# keycontrol2.net
KiCad netlist of a schematic drawn in Altium Designer
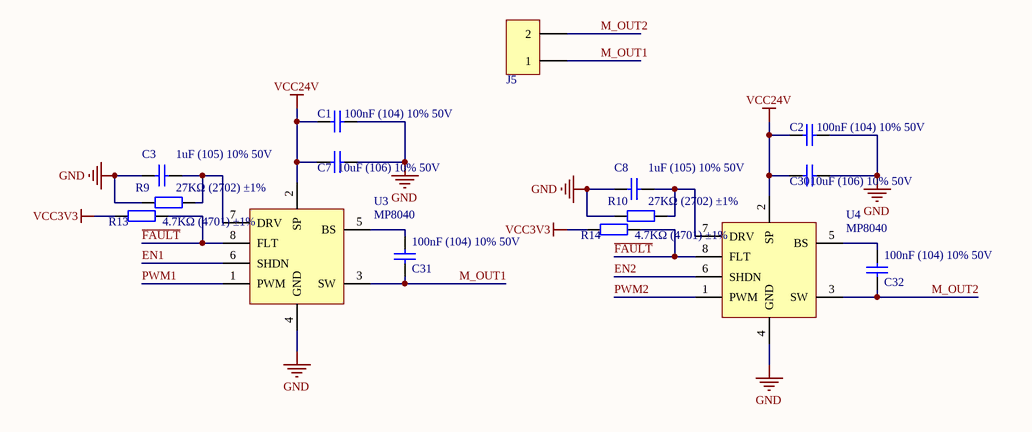
[diagram p0: keycontrol2.SchDoc]

(export (version "E")
  (design (tool "Eeschema 10.0.6"))
  (components
    (comp (ref "C1")
      (value "100nF (104) 10% 50V")
      (footprint "0603_C")
      (description "贴片电容")
      (libsource (lib "AD封装2018.9.19Miscellaneous Devices LC") (part "0603 100nF (104) 10% 50V"))
    )
    (comp (ref "C2")
      (value "100nF (104) 10% 50V")
      (footprint "0603_C")
      (description "贴片电容")
      (libsource (lib "AD封装2018.9.19Miscellaneous Devices LC") (part "0603 100nF (104) 10% 50V"))
    )
    (comp (ref "C3")
      (value "1uF (105) 10% 50V")
      (footprint "0603_C")
      (description "贴片电容")
      (libsource (lib "AD封装2018.9.19Miscellaneous Devices LC") (part "0603 1uF (105) 10% 50V"))
    )
    (comp (ref "C7")
      (value "10uF (106) 10% 50V")
      (footprint "1206_C")
      (description "贴片电容")
      (libsource (lib "AD封装2018.9.19Miscellaneous Devices LC") (part "1206 10uF (106) 10% 50V"))
    )
    (comp (ref "C8")
      (value "1uF (105) 10% 50V")
      (footprint "0603_C")
      (description "贴片电容")
      (libsource (lib "AD封装2018.9.19Miscellaneous Devices LC") (part "0603 1uF (105) 10% 50V"))
    )
    (comp (ref "C30")
      (value "10uF (106) 10% 50V")
      (footprint "1206_C")
      (description "贴片电容")
      (libsource (lib "AD封装2018.9.19Miscellaneous Devices LC") (part "1206 10uF (106) 10% 50V"))
    )
    (comp (ref "C31")
      (value "100nF (104) 10% 50V")
      (footprint "0603_C")
      (description "贴片电容")
      (libsource (lib "AD封装2018.9.19Miscellaneous Devices LC") (part "0603 100nF (104) 10% 50V"))
    )
    (comp (ref "C32")
      (value "100nF (104) 10% 50V")
      (footprint "0603_C")
      (description "贴片电容")
      (libsource (lib "AD封装2018.9.19Miscellaneous Devices LC") (part "0603 100nF (104) 10% 50V"))
    )
    (comp (ref "J5") (value "MOTOR") (footprint "XH-2P") (libsource (lib "我的集成库") (part "header2")))
    (comp (ref "R9")
      (value "27KΩ (2702) ±1%")
      (footprint "0603_R")
      (description "贴片电阻")
      (libsource (lib "AD封装2018.9.19Miscellaneous Devices LC") (part "0603 27KΩ (2702) 1%"))
    )
    (comp (ref "R10")
      (value "27KΩ (2702) ±1%")
      (footprint "0603_R")
      (description "贴片电阻")
      (libsource (lib "AD封装2018.9.19Miscellaneous Devices LC") (part "0603 27KΩ (2702) 1%"))
    )
    (comp (ref "R13")
      (value "4.7KΩ (4701) ±1%")
      (footprint "0603_R")
      (description "贴片电阻")
      (libsource (lib "AD封装2018.9.19Miscellaneous Devices LC") (part "0603 4.7KΩ (4701) 1%"))
    )
    (comp (ref "R14")
      (value "4.7KΩ (4701) ±1%")
      (footprint "0603_R")
      (description "贴片电阻")
      (libsource (lib "AD封装2018.9.19Miscellaneous Devices LC") (part "0603 4.7KΩ (4701) 1%"))
    )
    (comp (ref "U3")
      (value "MP8040")
      (footprint "SOIC-8_150mil")
      (description "half bridge power driver")
      (libsource (lib "我的集成库") (part "MP8040DN-LF-Z"))
    )
    (comp (ref "U4")
      (value "MP8040")
      (footprint "SOIC-8_150mil")
      (description "half bridge power driver")
      (libsource (lib "我的集成库") (part "MP8040DN-LF-Z"))
    )
  )
  (nets
    (net (code "1") (name "/EN1") (class "Default")
      (node (ref "U3") (pin "6") (pinfunction "SHDN_6") (pintype "passive"))
    )
    (net (code "2") (name "/EN2") (class "Default")
      (node (ref "U4") (pin "6") (pinfunction "SHDN_6") (pintype "passive"))
    )
    (net (code "3") (name "/M_OUT1") (class "Default")
      (node (ref "C31") (pin "1") (pinfunction "1_1") (pintype "passive"))
      (node (ref "J5") (pin "1") (pinfunction "1_1") (pintype "passive"))
      (node (ref "U3") (pin "3") (pinfunction "SW_3") (pintype "passive"))
    )
    (net (code "4") (name "/M_OUT2") (class "Default")
      (node (ref "C32") (pin "1") (pinfunction "1_1") (pintype "passive"))
      (node (ref "J5") (pin "2") (pinfunction "2_2") (pintype "passive"))
      (node (ref "U4") (pin "3") (pinfunction "SW_3") (pintype "passive"))
    )
    (net (code "5") (name "/PWM1") (class "Default")
      (node (ref "U3") (pin "1") (pinfunction "PWM_1") (pintype "passive"))
    )
    (net (code "6") (name "/PWM2") (class "Default")
      (node (ref "U4") (pin "1") (pinfunction "PWM_1") (pintype "passive"))
    )
    (net (code "7") (name "/~{FAULT}") (class "Default")
      (node (ref "R13") (pin "2") (pinfunction "2_2") (pintype "passive"))
      (node (ref "R14") (pin "2") (pinfunction "2_2") (pintype "passive"))
      (node (ref "U3") (pin "8") (pinfunction "FLT_8") (pintype "passive"))
      (node (ref "U4") (pin "8") (pinfunction "FLT_8") (pintype "passive"))
    )
    (net (code "8") (name "GND") (class "Default")
      (node (ref "C1") (pin "1") (pinfunction "1_1") (pintype "passive"))
      (node (ref "C2") (pin "1") (pinfunction "1_1") (pintype "passive"))
      (node (ref "C3") (pin "1") (pinfunction "1_1") (pintype "passive"))
      (node (ref "C30") (pin "2") (pinfunction "2_2") (pintype "passive"))
      (node (ref "C7") (pin "2") (pinfunction "2_2") (pintype "passive"))
      (node (ref "C8") (pin "1") (pinfunction "1_1") (pintype "passive"))
      (node (ref "R10") (pin "1") (pinfunction "1_1") (pintype "passive"))
      (node (ref "R9") (pin "1") (pinfunction "1_1") (pintype "passive"))
      (node (ref "U3") (pin "4") (pinfunction "GND_4") (pintype "passive"))
      (node (ref "U4") (pin "4") (pinfunction "GND_4") (pintype "passive"))
    )
    (net (code "9") (name "Net-(U3-BS)") (class "Default")
      (node (ref "C31") (pin "2") (pinfunction "2_2") (pintype "passive"))
      (node (ref "U3") (pin "5") (pinfunction "BS_5") (pintype "passive"))
    )
    (net (code "10") (name "Net-(U3-DRV)") (class "Default")
      (node (ref "C3") (pin "2") (pinfunction "2_2") (pintype "passive"))
      (node (ref "R9") (pin "2") (pinfunction "2_2") (pintype "passive"))
      (node (ref "U3") (pin "7") (pinfunction "DRV_7") (pintype "passive"))
    )
    (net (code "11") (name "Net-(U4-BS)") (class "Default")
      (node (ref "C32") (pin "2") (pinfunction "2_2") (pintype "passive"))
      (node (ref "U4") (pin "5") (pinfunction "BS_5") (pintype "passive"))
    )
    (net (code "12") (name "Net-(U4-DRV)") (class "Default")
      (node (ref "C8") (pin "2") (pinfunction "2_2") (pintype "passive"))
      (node (ref "R10") (pin "2") (pinfunction "2_2") (pintype "passive"))
      (node (ref "U4") (pin "7") (pinfunction "DRV_7") (pintype "passive"))
    )
    (net (code "13") (name "VCC3V3") (class "Default")
      (node (ref "R13") (pin "1") (pinfunction "1_1") (pintype "passive"))
      (node (ref "R14") (pin "1") (pinfunction "1_1") (pintype "passive"))
    )
    (net (code "14") (name "VCC24V") (class "Default")
      (node (ref "C1") (pin "2") (pinfunction "2_2") (pintype "passive"))
      (node (ref "C2") (pin "2") (pinfunction "2_2") (pintype "passive"))
      (node (ref "C30") (pin "1") (pinfunction "1_1") (pintype "passive"))
      (node (ref "C7") (pin "1") (pinfunction "1_1") (pintype "passive"))
      (node (ref "U3") (pin "2") (pinfunction "SP_2") (pintype "passive"))
      (node (ref "U4") (pin "2") (pinfunction "SP_2") (pintype "passive"))
    )
  )
)
